# main.net
KiCad netlist of a schematic drawn in EAGLE
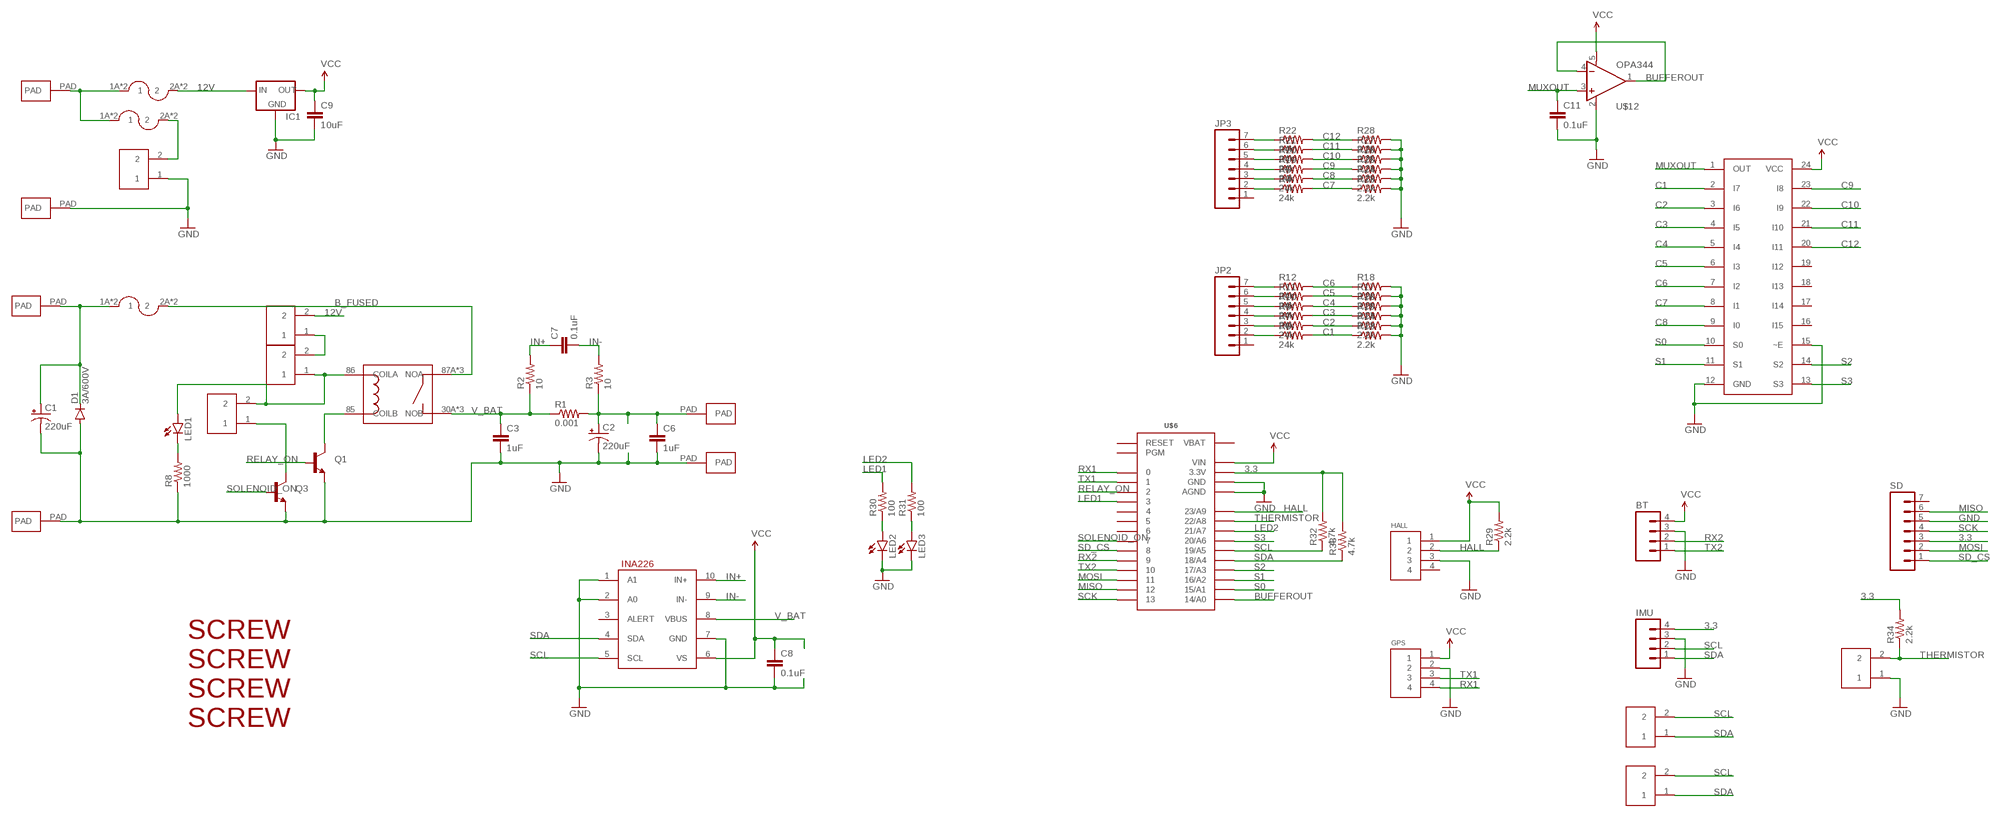
[diagram p0: schematic, sheet 1]

(export (version "E")
  (design (tool "Eeschema 10.0.6"))
  (components
    (comp (ref "BT")
      (value "M04PTH")
      (footprint "eagle-import:1X04")
      (libsource (lib "eagle-import") (part "M04PTH"))
    )
    (comp (ref "C1")
      (value "220uF")
      (footprint "eagle-import:CPOL-RADIAL-1000UF-25V")
      (libsource (lib "eagle-import") (part "CAP_POLPTH4"))
    )
    (comp (ref "C2")
      (value "220uF")
      (footprint "eagle-import:CPOL-RADIAL-1000UF-25V")
      (libsource (lib "eagle-import") (part "CAP_POLPTH4"))
    )
    (comp (ref "C3")
      (value "1uF")
      (footprint "eagle-import:1206")
      (libsource (lib "eagle-import") (part "CAP1206"))
    )
    (comp (ref "C6")
      (value "1uF")
      (footprint "eagle-import:1206")
      (libsource (lib "eagle-import") (part "CAP1206"))
    )
    (comp (ref "C7")
      (value "0.1uF")
      (footprint "eagle-import:0603-CAP")
      (libsource (lib "eagle-import") (part "SparkFun-Passives_CAP0603-CAP"))
    )
    (comp (ref "C8")
      (value "0.1uF")
      (footprint "eagle-import:0603-CAP")
      (libsource (lib "eagle-import") (part "SparkFun-Passives_CAP0603-CAP"))
    )
    (comp (ref "C9")
      (value "10uF")
      (footprint "eagle-import:0805")
      (libsource (lib "eagle-import") (part "SparkFun-Passives_CAP0805"))
    )
    (comp (ref "C11")
      (value "0.1uF")
      (footprint "eagle-import:0603-CAP")
      (libsource (lib "eagle-import") (part "SparkFun-Passives_CAP0603-CAP"))
    )
    (comp (ref "D1")
      (value "3A/600V")
      (footprint "eagle-import:SMC")
      (libsource (lib "eagle-import") (part "DIODEES3J"))
    )
    (comp (ref "GPS")
      (value "GPS")
      (footprint "eagle-import:4PINVALULOK")
      (libsource (lib "eagle-import") (part "HEADER4VALULOK"))
    )
    (comp (ref "HALL")
      (value "HEADER4VALULOK")
      (footprint "eagle-import:4PINVALULOK")
      (libsource (lib "eagle-import") (part "HEADER4VALULOK"))
    )
    (comp (ref "IC1")
      (value "V_REG_78XXSINK")
      (footprint "eagle-import:TO220-IGO")
      (libsource (lib "eagle-import") (part "V_REG_78XXSINK"))
    )
    (comp (ref "IMU")
      (value "M04PTH")
      (footprint "eagle-import:1X04")
      (libsource (lib "eagle-import") (part "M04PTH"))
    )
    (comp (ref "JP2")
      (value "M07")
      (footprint "eagle-import:1X07")
      (libsource (lib "eagle-import") (part "M07"))
    )
    (comp (ref "JP3")
      (value "M07")
      (footprint "eagle-import:1X07")
      (libsource (lib "eagle-import") (part "M07"))
    )
    (comp (ref "LED1")
      (value "LED1206")
      (footprint "eagle-import:LED-1206")
      (libsource (lib "eagle-import") (part "LED1206"))
    )
    (comp (ref "LED2")
      (value "LED1206")
      (footprint "eagle-import:LED-1206")
      (libsource (lib "eagle-import") (part "LED1206"))
    )
    (comp (ref "LED3")
      (value "LED1206")
      (footprint "eagle-import:LED-1206")
      (libsource (lib "eagle-import") (part "LED1206"))
    )
    (comp (ref "Q1")
      (value "TRANSISTOR_NPNSMD2")
      (footprint "eagle-import:SOT223")
      (libsource (lib "eagle-import") (part "TRANSISTOR_NPNSMD2"))
    )
    (comp (ref "Q3")
      (value "TRANSISTOR_NPNSMD2")
      (footprint "eagle-import:SOT223")
      (libsource (lib "eagle-import") (part "TRANSISTOR_NPNSMD2"))
    )
    (comp (ref "R1")
      (value "0.001")
      (footprint "eagle-import:R2512")
      (libsource (lib "eagle-import") (part "SparkFun-Resistors_RESISTOR2512"))
    )
    (comp (ref "R2")
      (value "10")
      (footprint "eagle-import:0603-RES")
      (libsource (lib "eagle-import") (part "RESISTOR0603-RES"))
    )
    (comp (ref "R3")
      (value "10")
      (footprint "eagle-import:0603-RES")
      (libsource (lib "eagle-import") (part "RESISTOR0603-RES"))
    )
    (comp (ref "R4")
      (value "24k")
      (footprint "eagle-import:0603-RES")
      (libsource (lib "eagle-import") (part "RESISTOR0603-RES"))
    )
    (comp (ref "R5")
      (value "24k")
      (footprint "eagle-import:0603-RES")
      (libsource (lib "eagle-import") (part "RESISTOR0603-RES"))
    )
    (comp (ref "R6")
      (value "24k")
      (footprint "eagle-import:0603-RES")
      (libsource (lib "eagle-import") (part "RESISTOR0603-RES"))
    )
    (comp (ref "R7")
      (value "24k")
      (footprint "eagle-import:0603-RES")
      (libsource (lib "eagle-import") (part "RESISTOR0603-RES"))
    )
    (comp (ref "R8")
      (value "1000")
      (footprint "eagle-import:0603-RES")
      (libsource (lib "eagle-import") (part "RESISTOR0603-RES"))
    )
    (comp (ref "R9")
      (value "24k")
      (footprint "eagle-import:0603-RES")
      (libsource (lib "eagle-import") (part "RESISTOR0603-RES"))
    )
    (comp (ref "R10")
      (value "24k")
      (footprint "eagle-import:0603-RES")
      (libsource (lib "eagle-import") (part "RESISTOR0603-RES"))
    )
    (comp (ref "R11")
      (value "24k")
      (footprint "eagle-import:0603-RES")
      (libsource (lib "eagle-import") (part "RESISTOR0603-RES"))
    )
    (comp (ref "R12")
      (value "24k")
      (footprint "eagle-import:0603-RES")
      (libsource (lib "eagle-import") (part "RESISTOR0603-RES"))
    )
    (comp (ref "R13")
      (value "2.2k")
      (footprint "eagle-import:0603-RES")
      (libsource (lib "eagle-import") (part "RESISTOR0603-RES"))
    )
    (comp (ref "R14")
      (value "2.2k")
      (footprint "eagle-import:0603-RES")
      (libsource (lib "eagle-import") (part "RESISTOR0603-RES"))
    )
    (comp (ref "R15")
      (value "2.2k")
      (footprint "eagle-import:0603-RES")
      (libsource (lib "eagle-import") (part "RESISTOR0603-RES"))
    )
    (comp (ref "R16")
      (value "2.2k")
      (footprint "eagle-import:0603-RES")
      (libsource (lib "eagle-import") (part "RESISTOR0603-RES"))
    )
    (comp (ref "R17")
      (value "2.2k")
      (footprint "eagle-import:0603-RES")
      (libsource (lib "eagle-import") (part "RESISTOR0603-RES"))
    )
    (comp (ref "R18")
      (value "2.2k")
      (footprint "eagle-import:0603-RES")
      (libsource (lib "eagle-import") (part "RESISTOR0603-RES"))
    )
    (comp (ref "R19")
      (value "24k")
      (footprint "eagle-import:0603-RES")
      (libsource (lib "eagle-import") (part "RESISTOR0603-RES"))
    )
    (comp (ref "R20")
      (value "24k")
      (footprint "eagle-import:0603-RES")
      (libsource (lib "eagle-import") (part "RESISTOR0603-RES"))
    )
    (comp (ref "R21")
      (value "24k")
      (footprint "eagle-import:0603-RES")
      (libsource (lib "eagle-import") (part "RESISTOR0603-RES"))
    )
    (comp (ref "R22")
      (value "24k")
      (footprint "eagle-import:0603-RES")
      (libsource (lib "eagle-import") (part "RESISTOR0603-RES"))
    )
    (comp (ref "R23")
      (value "2.2k")
      (footprint "eagle-import:0603-RES")
      (libsource (lib "eagle-import") (part "RESISTOR0603-RES"))
    )
    (comp (ref "R24")
      (value "2.2k")
      (footprint "eagle-import:0603-RES")
      (libsource (lib "eagle-import") (part "RESISTOR0603-RES"))
    )
    (comp (ref "R25")
      (value "2.2k")
      (footprint "eagle-import:0603-RES")
      (libsource (lib "eagle-import") (part "RESISTOR0603-RES"))
    )
    (comp (ref "R26")
      (value "2.2k")
      (footprint "eagle-import:0603-RES")
      (libsource (lib "eagle-import") (part "RESISTOR0603-RES"))
    )
    (comp (ref "R27")
      (value "2.2k")
      (footprint "eagle-import:0603-RES")
      (libsource (lib "eagle-import") (part "RESISTOR0603-RES"))
    )
    (comp (ref "R28")
      (value "2.2k")
      (footprint "eagle-import:0603-RES")
      (libsource (lib "eagle-import") (part "RESISTOR0603-RES"))
    )
    (comp (ref "R29")
      (value "2.2k")
      (footprint "eagle-import:0603-RES")
      (libsource (lib "eagle-import") (part "RESISTOR0603-RES"))
    )
    (comp (ref "R30")
      (value "100")
      (footprint "eagle-import:0603-RES")
      (libsource (lib "eagle-import") (part "RESISTOR0603-RES"))
    )
    (comp (ref "R31")
      (value "100")
      (footprint "eagle-import:0603-RES")
      (libsource (lib "eagle-import") (part "RESISTOR0603-RES"))
    )
    (comp (ref "R32")
      (value "4.7k")
      (footprint "eagle-import:0603-RES")
      (libsource (lib "eagle-import") (part "RESISTOR0603-RES"))
    )
    (comp (ref "R33")
      (value "4.7k")
      (footprint "eagle-import:0603-RES")
      (libsource (lib "eagle-import") (part "RESISTOR0603-RES"))
    )
    (comp (ref "R34")
      (value "2.2k")
      (footprint "eagle-import:0603-RES")
      (libsource (lib "eagle-import") (part "RESISTOR0603-RES"))
    )
    (comp (ref "SD")
      (value "M07")
      (footprint "eagle-import:1X07")
      (libsource (lib "eagle-import") (part "M07"))
    )
    (comp (ref "U$1")
      (value "INA226")
      (footprint "eagle-import:PSOP-10")
      (libsource (lib "eagle-import") (part "INA226"))
    )
    (comp (ref "U$2")
      (value "PAD")
      (footprint "eagle-import:PAD")
      (libsource (lib "eagle-import") (part "PAD"))
    )
    (comp (ref "U$3")
      (value "PAD")
      (footprint "eagle-import:PAD")
      (libsource (lib "eagle-import") (part "PAD"))
    )
    (comp (ref "U$4")
      (value "PAD")
      (footprint "eagle-import:PAD")
      (libsource (lib "eagle-import") (part "PAD"))
    )
    (comp (ref "U$5")
      (value "PAD")
      (footprint "eagle-import:PAD")
      (libsource (lib "eagle-import") (part "PAD"))
    )
    (comp (ref "U$6")
      (value "TEENSY_3.0_BASIC")
      (footprint "eagle-import:TEENSY_3.0_BASIC")
      (libsource (lib "eagle-import") (part "TEENSY_3.0_BASIC"))
    )
    (comp (ref "U$7")
      (value "RELAY")
      (footprint "eagle-import:PANASONIC_HP_RELAY")
      (libsource (lib "eagle-import") (part "RELAY"))
    )
    (comp (ref "U$8")
      (value "FUSE")
      (footprint "eagle-import:AUTO_FUSE")
      (libsource (lib "eagle-import") (part "FUSE"))
    )
    (comp (ref "U$9")
      (value "HEADER2")
      (footprint "eagle-import:2PINVALULOK")
      (libsource (lib "eagle-import") (part "HEADER2"))
    )
    (comp (ref "U$10")
      (value "HEADER2")
      (footprint "eagle-import:2PINVALULOK")
      (libsource (lib "eagle-import") (part "HEADER2"))
    )
    (comp (ref "U$11")
      (value "CD74HC4067")
      (footprint "eagle-import:SO-24DW")
      (libsource (lib "eagle-import") (part "CD74HC4067"))
    )
    (comp (ref "U$12")
      (value "OPA344")
      (footprint "eagle-import:SOT23-5")
      (libsource (lib "eagle-import") (part "OPA344"))
    )
    (comp (ref "U$13")
      (value "SCREW")
      (footprint "eagle-import:M3HOLE")
      (libsource (lib "eagle-import") (part "SCREW"))
    )
    (comp (ref "U$14")
      (value "SCREW")
      (footprint "eagle-import:M3HOLE")
      (libsource (lib "eagle-import") (part "SCREW"))
    )
    (comp (ref "U$15")
      (value "SCREW")
      (footprint "eagle-import:M3HOLE")
      (libsource (lib "eagle-import") (part "SCREW"))
    )
    (comp (ref "U$16")
      (value "SCREW")
      (footprint "eagle-import:M3HOLE")
      (libsource (lib "eagle-import") (part "SCREW"))
    )
    (comp (ref "U$17")
      (value "HEADER2")
      (footprint "eagle-import:2PINVALULOK")
      (libsource (lib "eagle-import") (part "HEADER2"))
    )
    (comp (ref "U$18")
      (value "FUSE")
      (footprint "eagle-import:AUTO_FUSE")
      (libsource (lib "eagle-import") (part "FUSE"))
    )
    (comp (ref "U$19")
      (value "HEADER2")
      (footprint "eagle-import:2PINVALULOK")
      (libsource (lib "eagle-import") (part "HEADER2"))
    )
    (comp (ref "U$20")
      (value "PAD")
      (footprint "eagle-import:PAD")
      (libsource (lib "eagle-import") (part "PAD"))
    )
    (comp (ref "U$21")
      (value "PAD")
      (footprint "eagle-import:PAD")
      (libsource (lib "eagle-import") (part "PAD"))
    )
    (comp (ref "U$22")
      (value "FUSE")
      (footprint "eagle-import:AUTO_FUSE")
      (libsource (lib "eagle-import") (part "FUSE"))
    )
    (comp (ref "U$23")
      (value "HEADER2")
      (footprint "eagle-import:2PINVALULOK")
      (libsource (lib "eagle-import") (part "HEADER2"))
    )
    (comp (ref "U$24")
      (value "HEADER2")
      (footprint "eagle-import:2PINVALULOK")
      (libsource (lib "eagle-import") (part "HEADER2"))
    )
    (comp (ref "U$25")
      (value "HEADER2")
      (footprint "eagle-import:2PINVALULOK")
      (libsource (lib "eagle-import") (part "HEADER2"))
    )
  )
  (nets
    (net (code "1") (name "/3.3") (class "Default")
      (node (ref "IMU") (pin "4") (pinfunction "4_4") (pintype "passive"))
      (node (ref "R32") (pin "2") (pinfunction "2_2") (pintype "passive"))
      (node (ref "R33") (pin "2") (pinfunction "2_2") (pintype "passive"))
      (node (ref "R34") (pin "2") (pinfunction "2_2") (pintype "passive"))
      (node (ref "SD") (pin "3") (pinfunction "3_3") (pintype "passive"))
      (node (ref "U$6") (pin "3.3V") (pinfunction "3.3V_3.3V") (pintype "power_in"))
      (node (ref "U$6") (pin "3.3V1") (pinfunction "3.3V_3.3V1") (pintype "power_in"))
    )
    (net (code "2") (name "/12V") (class "Default")
      (node (ref "IC1") (pin "IN") (pinfunction "IN_IN") (pintype "input"))
      (node (ref "U$10") (pin "2") (pinfunction "2_2") (pintype "bidirectional"))
      (node (ref "U$22") (pin "2A") (pinfunction "2_2A") (pintype "bidirectional"))
      (node (ref "U$22") (pin "2B") (pinfunction "2_2B") (pintype "bidirectional"))
    )
    (net (code "3") (name "/BUFFEROUT") (class "Default")
      (node (ref "U$12") (pin "1") (pinfunction "OUT_1") (pintype "output"))
      (node (ref "U$12") (pin "4") (pinfunction "-IN_4") (pintype "input"))
      (node (ref "U$6") (pin "14/A0") (pinfunction "14/A0_14/A0") (pintype "bidirectional"))
    )
    (net (code "4") (name "/B_FUSED") (class "Default")
      (node (ref "U$7") (pin "87A") (pinfunction "NOA_87A") (pintype "bidirectional"))
      (node (ref "U$7") (pin "87B") (pinfunction "NOA_87B") (pintype "bidirectional"))
      (node (ref "U$7") (pin "87C") (pinfunction "NOA_87C") (pintype "bidirectional"))
      (node (ref "U$8") (pin "2A") (pinfunction "2_2A") (pintype "bidirectional"))
      (node (ref "U$8") (pin "2B") (pinfunction "2_2B") (pintype "bidirectional"))
    )
    (net (code "5") (name "/C1") (class "Default")
      (node (ref "R13") (pin "1") (pinfunction "1_1") (pintype "passive"))
      (node (ref "R6") (pin "2") (pinfunction "2_2") (pintype "passive"))
      (node (ref "U$11") (pin "2") (pinfunction "I7_2") (pintype "bidirectional"))
    )
    (net (code "6") (name "/C2") (class "Default")
      (node (ref "R14") (pin "1") (pinfunction "1_1") (pintype "passive"))
      (node (ref "R7") (pin "2") (pinfunction "2_2") (pintype "passive"))
      (node (ref "U$11") (pin "3") (pinfunction "I6_3") (pintype "bidirectional"))
    )
    (net (code "7") (name "/C3") (class "Default")
      (node (ref "R15") (pin "1") (pinfunction "1_1") (pintype "passive"))
      (node (ref "R9") (pin "2") (pinfunction "2_2") (pintype "passive"))
      (node (ref "U$11") (pin "4") (pinfunction "I5_4") (pintype "bidirectional"))
    )
    (net (code "8") (name "/C4") (class "Default")
      (node (ref "R10") (pin "2") (pinfunction "2_2") (pintype "passive"))
      (node (ref "R16") (pin "1") (pinfunction "1_1") (pintype "passive"))
      (node (ref "U$11") (pin "5") (pinfunction "I4_5") (pintype "bidirectional"))
    )
    (net (code "9") (name "/C5") (class "Default")
      (node (ref "R11") (pin "2") (pinfunction "2_2") (pintype "passive"))
      (node (ref "R17") (pin "1") (pinfunction "1_1") (pintype "passive"))
      (node (ref "U$11") (pin "6") (pinfunction "I3_6") (pintype "bidirectional"))
    )
    (net (code "10") (name "/C6") (class "Default")
      (node (ref "R12") (pin "2") (pinfunction "2_2") (pintype "passive"))
      (node (ref "R18") (pin "1") (pinfunction "1_1") (pintype "passive"))
      (node (ref "U$11") (pin "7") (pinfunction "I2_7") (pintype "bidirectional"))
    )
    (net (code "11") (name "/C7") (class "Default")
      (node (ref "R23") (pin "1") (pinfunction "1_1") (pintype "passive"))
      (node (ref "R4") (pin "2") (pinfunction "2_2") (pintype "passive"))
      (node (ref "U$11") (pin "8") (pinfunction "I1_8") (pintype "bidirectional"))
    )
    (net (code "12") (name "/C8") (class "Default")
      (node (ref "R24") (pin "1") (pinfunction "1_1") (pintype "passive"))
      (node (ref "R5") (pin "2") (pinfunction "2_2") (pintype "passive"))
      (node (ref "U$11") (pin "9") (pinfunction "I0_9") (pintype "bidirectional"))
    )
    (net (code "13") (name "/C9") (class "Default")
      (node (ref "R19") (pin "2") (pinfunction "2_2") (pintype "passive"))
      (node (ref "R25") (pin "1") (pinfunction "1_1") (pintype "passive"))
      (node (ref "U$11") (pin "23") (pinfunction "I8_23") (pintype "bidirectional"))
    )
    (net (code "14") (name "/C10") (class "Default")
      (node (ref "R20") (pin "2") (pinfunction "2_2") (pintype "passive"))
      (node (ref "R26") (pin "1") (pinfunction "1_1") (pintype "passive"))
      (node (ref "U$11") (pin "22") (pinfunction "I9_22") (pintype "bidirectional"))
    )
    (net (code "15") (name "/C11") (class "Default")
      (node (ref "R21") (pin "2") (pinfunction "2_2") (pintype "passive"))
      (node (ref "R27") (pin "1") (pinfunction "1_1") (pintype "passive"))
      (node (ref "U$11") (pin "21") (pinfunction "I10_21") (pintype "bidirectional"))
    )
    (net (code "16") (name "/C12") (class "Default")
      (node (ref "R22") (pin "2") (pinfunction "2_2") (pintype "passive"))
      (node (ref "R28") (pin "1") (pinfunction "1_1") (pintype "passive"))
      (node (ref "U$11") (pin "20") (pinfunction "I11_20") (pintype "bidirectional"))
    )
    (net (code "17") (name "/HALL") (class "Default")
      (node (ref "HALL") (pin "2") (pinfunction "2_2") (pintype "bidirectional"))
      (node (ref "R29") (pin "1") (pinfunction "1_1") (pintype "passive"))
      (node (ref "U$6") (pin "23/A9") (pinfunction "23/A9_23/A9") (pintype "bidirectional"))
    )
    (net (code "18") (name "/IN+") (class "Default")
      (node (ref "C7") (pin "1") (pinfunction "1_1") (pintype "passive"))
      (node (ref "R2") (pin "2") (pinfunction "2_2") (pintype "passive"))
      (node (ref "U$1") (pin "10") (pinfunction "IN+_10") (pintype "bidirectional"))
    )
    (net (code "19") (name "/IN-") (class "Default")
      (node (ref "C7") (pin "2") (pinfunction "2_2") (pintype "passive"))
      (node (ref "R3") (pin "2") (pinfunction "2_2") (pintype "passive"))
      (node (ref "U$1") (pin "9") (pinfunction "IN-_9") (pintype "bidirectional"))
    )
    (net (code "20") (name "/LED1") (class "Default")
      (node (ref "R30") (pin "2") (pinfunction "2_2") (pintype "passive"))
      (node (ref "U$6") (pin "3") (pinfunction "3_3") (pintype "bidirectional"))
    )
    (net (code "21") (name "/LED2") (class "Default")
      (node (ref "R31") (pin "2") (pinfunction "2_2") (pintype "passive"))
      (node (ref "U$6") (pin "21/A7") (pinfunction "21/A7_21/A7") (pintype "bidirectional"))
    )
    (net (code "22") (name "/MISO") (class "Default")
      (node (ref "SD") (pin "6") (pinfunction "6_6") (pintype "passive"))
      (node (ref "U$6") (pin "12") (pinfunction "12_12") (pintype "bidirectional"))
    )
    (net (code "23") (name "/MOSI") (class "Default")
      (node (ref "SD") (pin "2") (pinfunction "2_2") (pintype "passive"))
      (node (ref "U$6") (pin "11") (pinfunction "11_11") (pintype "bidirectional"))
    )
    (net (code "24") (name "/MUXOUT") (class "Default")
      (node (ref "C11") (pin "1") (pinfunction "1_1") (pintype "passive"))
      (node (ref "U$11") (pin "1") (pinfunction "OUT_1") (pintype "bidirectional"))
      (node (ref "U$12") (pin "3") (pinfunction "+IN_3") (pintype "input"))
    )
    (net (code "25") (name "/RELAY_ON") (class "Default")
      (node (ref "Q1") (pin "1") (pinfunction "B_1") (pintype "passive"))
      (node (ref "U$6") (pin "2") (pinfunction "2_2") (pintype "bidirectional"))
    )
    (net (code "26") (name "/RX1") (class "Default")
      (node (ref "GPS") (pin "4") (pinfunction "4_4") (pintype "bidirectional"))
      (node (ref "U$6") (pin "0") (pinfunction "0_0") (pintype "bidirectional"))
    )
    (net (code "27") (name "/RX2") (class "Default")
      (node (ref "BT") (pin "2") (pinfunction "2_2") (pintype "passive"))
      (node (ref "U$6") (pin "9") (pinfunction "9_9") (pintype "bidirectional"))
    )
    (net (code "28") (name "/S0") (class "Default")
      (node (ref "U$11") (pin "10") (pinfunction "S0_10") (pintype "bidirectional"))
      (node (ref "U$6") (pin "15/A1") (pinfunction "15/A1_15/A1") (pintype "bidirectional"))
    )
    (net (code "29") (name "/S1") (class "Default")
      (node (ref "U$11") (pin "11") (pinfunction "S1_11") (pintype "bidirectional"))
      (node (ref "U$6") (pin "16/A2") (pinfunction "16/A2_16/A2") (pintype "bidirectional"))
    )
    (net (code "30") (name "/S2") (class "Default")
      (node (ref "U$11") (pin "14") (pinfunction "S2_14") (pintype "bidirectional"))
      (node (ref "U$6") (pin "17/A3") (pinfunction "17/A3_17/A3") (pintype "bidirectional"))
    )
    (net (code "31") (name "/S3") (class "Default")
      (node (ref "U$11") (pin "13") (pinfunction "S3_13") (pintype "bidirectional"))
      (node (ref "U$6") (pin "20/A6") (pinfunction "20/A6_20/A6") (pintype "bidirectional"))
    )
    (net (code "32") (name "/SCK") (class "Default")
      (node (ref "SD") (pin "4") (pinfunction "4_4") (pintype "passive"))
      (node (ref "U$6") (pin "13") (pinfunction "13_13") (pintype "bidirectional"))
    )
    (net (code "33") (name "/SCL") (class "Default")
      (node (ref "IMU") (pin "2") (pinfunction "2_2") (pintype "passive"))
      (node (ref "R32") (pin "1") (pinfunction "1_1") (pintype "passive"))
      (node (ref "U$1") (pin "5") (pinfunction "SCL_5") (pintype "bidirectional"))
      (node (ref "U$24") (pin "2") (pinfunction "2_2") (pintype "bidirectional"))
      (node (ref "U$25") (pin "2") (pinfunction "2_2") (pintype "bidirectional"))
      (node (ref "U$6") (pin "19/A5") (pinfunction "19/A5_19/A5") (pintype "bidirectional"))
    )
    (net (code "34") (name "/SDA") (class "Default")
      (node (ref "IMU") (pin "1") (pinfunction "1_1") (pintype "passive"))
      (node (ref "R33") (pin "1") (pinfunction "1_1") (pintype "passive"))
      (node (ref "U$1") (pin "4") (pinfunction "SDA_4") (pintype "bidirectional"))
      (node (ref "U$24") (pin "1") (pinfunction "1_1") (pintype "bidirectional"))
      (node (ref "U$25") (pin "1") (pinfunction "1_1") (pintype "bidirectional"))
      (node (ref "U$6") (pin "18/A4") (pinfunction "18/A4_18/A4") (pintype "bidirectional"))
    )
    (net (code "35") (name "/SD_CS") (class "Default")
      (node (ref "SD") (pin "1") (pinfunction "1_1") (pintype "passive"))
      (node (ref "U$6") (pin "8") (pinfunction "8_8") (pintype "bidirectional"))
    )
    (net (code "36") (name "/SOLENOID_ON") (class "Default")
      (node (ref "Q3") (pin "1") (pinfunction "B_1") (pintype "passive"))
      (node (ref "U$6") (pin "7") (pinfunction "7_7") (pintype "bidirectional"))
    )
    (net (code "37") (name "/THERMISTOR") (class "Default")
      (node (ref "R34") (pin "1") (pinfunction "1_1") (pintype "passive"))
      (node (ref "U$17") (pin "2") (pinfunction "2_2") (pintype "bidirectional"))
      (node (ref "U$6") (pin "22/A8") (pinfunction "22/A8_22/A8") (pintype "bidirectional"))
    )
    (net (code "38") (name "/TX1") (class "Default")
      (node (ref "GPS") (pin "3") (pinfunction "3_3") (pintype "bidirectional"))
      (node (ref "U$6") (pin "1") (pinfunction "1_1") (pintype "bidirectional"))
    )
    (net (code "39") (name "/TX2") (class "Default")
      (node (ref "BT") (pin "1") (pinfunction "1_1") (pintype "passive"))
      (node (ref "U$6") (pin "10") (pinfunction "10_10") (pintype "bidirectional"))
    )
    (net (code "40") (name "/VBAT") (class "Default")
      (node (ref "U$6") (pin "VBAT") (pinfunction "VBAT_VBAT") (pintype "power_in"))
    )
    (net (code "41") (name "/V_BAT") (class "Default")
      (node (ref "C3") (pin "1") (pinfunction "1_1") (pintype "passive"))
      (node (ref "R1") (pin "1") (pinfunction "1_1") (pintype "passive"))
      (node (ref "R2") (pin "1") (pinfunction "1_1") (pintype "passive"))
      (node (ref "U$1") (pin "8") (pinfunction "VBUS_8") (pintype "bidirectional"))
      (node (ref "U$7") (pin "30A") (pinfunction "NOB_30A") (pintype "bidirectional"))
      (node (ref "U$7") (pin "30B") (pinfunction "NOB_30B") (pintype "bidirectional"))
      (node (ref "U$7") (pin "30C") (pinfunction "NOB_30C") (pintype "bidirectional"))
    )
    (net (code "42") (name "GND") (class "Default")
      (node (ref "BT") (pin "3") (pinfunction "3_3") (pintype "passive"))
      (node (ref "C1") (pin "-") (pinfunction "-_-") (pintype "passive"))
      (node (ref "C11") (pin "2") (pinfunction "2_2") (pintype "passive"))
      (node (ref "C2") (pin "-") (pinfunction "-_-") (pintype "passive"))
      (node (ref "C3") (pin "2") (pinfunction "2_2") (pintype "passive"))
      (node (ref "C6") (pin "2") (pinfunction "2_2") (pintype "passive"))
      (node (ref "C8") (pin "2") (pinfunction "2_2") (pintype "passive"))
      (node (ref "C9") (pin "2") (pinfunction "2_2") (pintype "passive"))
      (node (ref "D1") (pin "A") (pinfunction "A_A") (pintype "passive"))
      (node (ref "GPS") (pin "2") (pinfunction "2_2") (pintype "bidirectional"))
      (node (ref "HALL") (pin "3") (pinfunction "3_3") (pintype "bidirectional"))
      (node (ref "IC1") (pin "GND") (pinfunction "GND_GND") (pintype "input"))
      (node (ref "IMU") (pin "3") (pinfunction "3_3") (pintype "passive"))
      (node (ref "LED2") (pin "C") (pinfunction "C_C") (pintype "passive"))
      (node (ref "LED3") (pin "C") (pinfunction "C_C") (pintype "passive"))
      (node (ref "Q1") (pin "3") (pinfunction "E_3") (pintype "passive"))
      (node (ref "Q3") (pin "3") (pinfunction "E_3") (pintype "passive"))
      (node (ref "R13") (pin "2") (pinfunction "2_2") (pintype "passive"))
      (node (ref "R14") (pin "2") (pinfunction "2_2") (pintype "passive"))
      (node (ref "R15") (pin "2") (pinfunction "2_2") (pintype "passive"))
      (node (ref "R16") (pin "2") (pinfunction "2_2") (pintype "passive"))
      (node (ref "R17") (pin "2") (pinfunction "2_2") (pintype "passive"))
      (node (ref "R18") (pin "2") (pinfunction "2_2") (pintype "passive"))
      (node (ref "R23") (pin "2") (pinfunction "2_2") (pintype "passive"))
      (node (ref "R24") (pin "2") (pinfunction "2_2") (pintype "passive"))
      (node (ref "R25") (pin "2") (pinfunction "2_2") (pintype "passive"))
      (node (ref "R26") (pin "2") (pinfunction "2_2") (pintype "passive"))
      (node (ref "R27") (pin "2") (pinfunction "2_2") (pintype "passive"))
      (node (ref "R28") (pin "2") (pinfunction "2_2") (pintype "passive"))
      (node (ref "R8") (pin "1") (pinfunction "1_1") (pintype "passive"))
      (node (ref "SD") (pin "5") (pinfunction "5_5") (pintype "passive"))
      (node (ref "U$1") (pin "1") (pinfunction "A1_1") (pintype "bidirectional"))
      (node (ref "U$1") (pin "2") (pinfunction "A0_2") (pintype "bidirectional"))
      (node (ref "U$1") (pin "7") (pinfunction "GND_7") (pintype "bidirectional"))
      (node (ref "U$11") (pin "12") (pinfunction "GND_12") (pintype "bidirectional"))
      (node (ref "U$11") (pin "15") (pinfunction "~{E}_15") (pintype "bidirectional"))
      (node (ref "U$12") (pin "2") (pinfunction "V-_2") (pintype "power_in"))
      (node (ref "U$17") (pin "1") (pinfunction "1_1") (pintype "bidirectional"))
      (node (ref "U$19") (pin "1") (pinfunction "1_1") (pintype "bidirectional"))
      (node (ref "U$21") (pin "PAD") (pinfunction "PAD_PAD") (pintype "bidirectional"))
      (node (ref "U$3") (pin "PAD") (pinfunction "PAD_PAD") (pintype "bidirectional"))
      (node (ref "U$5") (pin "PAD") (pinfunction "PAD_PAD") (pintype "bidirectional"))
      (node (ref "U$6") (pin "AGND") (pinfunction "AGND_AGND") (pintype "power_in"))
      (node (ref "U$6") (pin "GND") (pinfunction "GND_GND") (pintype "power_in"))
      (node (ref "U$6") (pin "GND1") (pinfunction "GND_GND1") (pintype "power_in"))
    )
    (net (code "43") (name "Net-(C1-Pad+)") (class "Default")
      (node (ref "C1") (pin "+") (pinfunction "+_+") (pintype "passive"))
      (node (ref "D1") (pin "C") (pinfunction "C_C") (pintype "passive"))
      (node (ref "U$2") (pin "PAD") (pinfunction "PAD_PAD") (pintype "bidirectional"))
      (node (ref "U$8") (pin "1A") (pinfunction "1_1A") (pintype "bidirectional"))
      (node (ref "U$8") (pin "1B") (pinfunction "1_1B") (pintype "bidirectional"))
    )
    (net (code "44") (name "Net-(C2-Pad+)") (class "Default")
      (node (ref "C2") (pin "+") (pinfunction "+_+") (pintype "passive"))
      (node (ref "C6") (pin "1") (pinfunction "1_1") (pintype "passive"))
      (node (ref "R1") (pin "2") (pinfunction "2_2") (pintype "passive"))
      (node (ref "R3") (pin "1") (pinfunction "1_1") (pintype "passive"))
      (node (ref "U$4") (pin "PAD") (pinfunction "PAD_PAD") (pintype "bidirectional"))
    )
    (net (code "45") (name "Net-(JP2-Pad2)") (class "Default")
      (node (ref "JP2") (pin "2") (pinfunction "2_2") (pintype "passive"))
      (node (ref "R6") (pin "1") (pinfunction "1_1") (pintype "passive"))
    )
    (net (code "46") (name "Net-(JP2-Pad3)") (class "Default")
      (node (ref "JP2") (pin "3") (pinfunction "3_3") (pintype "passive"))
      (node (ref "R7") (pin "1") (pinfunction "1_1") (pintype "passive"))
    )
    (net (code "47") (name "Net-(JP2-Pad4)") (class "Default")
      (node (ref "JP2") (pin "4") (pinfunction "4_4") (pintype "passive"))
      (node (ref "R9") (pin "1") (pinfunction "1_1") (pintype "passive"))
    )
    (net (code "48") (name "Net-(JP2-Pad5)") (class "Default")
      (node (ref "JP2") (pin "5") (pinfunction "5_5") (pintype "passive"))
      (node (ref "R10") (pin "1") (pinfunction "1_1") (pintype "passive"))
    )
    (net (code "49") (name "Net-(JP2-Pad6)") (class "Default")
      (node (ref "JP2") (pin "6") (pinfunction "6_6") (pintype "passive"))
      (node (ref "R11") (pin "1") (pinfunction "1_1") (pintype "passive"))
    )
    (net (code "50") (name "Net-(JP2-Pad7)") (class "Default")
      (node (ref "JP2") (pin "7") (pinfunction "7_7") (pintype "passive"))
      (node (ref "R12") (pin "1") (pinfunction "1_1") (pintype "passive"))
    )
    (net (code "51") (name "Net-(JP3-Pad2)") (class "Default")
      (node (ref "JP3") (pin "2") (pinfunction "2_2") (pintype "passive"))
      (node (ref "R4") (pin "1") (pinfunction "1_1") (pintype "passive"))
    )
    (net (code "52") (name "Net-(JP3-Pad3)") (class "Default")
      (node (ref "JP3") (pin "3") (pinfunction "3_3") (pintype "passive"))
      (node (ref "R5") (pin "1") (pinfunction "1_1") (pintype "passive"))
    )
    (net (code "53") (name "Net-(JP3-Pad4)") (class "Default")
      (node (ref "JP3") (pin "4") (pinfunction "4_4") (pintype "passive"))
      (node (ref "R19") (pin "1") (pinfunction "1_1") (pintype "passive"))
    )
    (net (code "54") (name "Net-(JP3-Pad5)") (class "Default")
      (node (ref "JP3") (pin "5") (pinfunction "5_5") (pintype "passive"))
      (node (ref "R20") (pin "1") (pinfunction "1_1") (pintype "passive"))
    )
    (net (code "55") (name "Net-(JP3-Pad6)") (class "Default")
      (node (ref "JP3") (pin "6") (pinfunction "6_6") (pintype "passive"))
      (node (ref "R21") (pin "1") (pinfunction "1_1") (pintype "passive"))
    )
    (net (code "56") (name "Net-(JP3-Pad7)") (class "Default")
      (node (ref "JP3") (pin "7") (pinfunction "7_7") (pintype "passive"))
      (node (ref "R22") (pin "1") (pinfunction "1_1") (pintype "passive"))
    )
    (net (code "57") (name "Net-(LED1-PadC)") (class "Default")
      (node (ref "LED1") (pin "C") (pinfunction "C_C") (pintype "passive"))
      (node (ref "R8") (pin "2") (pinfunction "2_2") (pintype "passive"))
    )
    (net (code "58") (name "Net-(LED2-PadA)") (class "Default")
      (node (ref "LED2") (pin "A") (pinfunction "A_A") (pintype "passive"))
      (node (ref "R30") (pin "1") (pinfunction "1_1") (pintype "passive"))
    )
    (net (code "59") (name "Net-(LED3-PadA)") (class "Default")
      (node (ref "LED3") (pin "A") (pinfunction "A_A") (pintype "passive"))
      (node (ref "R31") (pin "1") (pinfunction "1_1") (pintype "passive"))
    )
    (net (code "60") (name "Net-(Q1-C)") (class "Default")
      (node (ref "Q1") (pin "2") (pinfunction "C_2") (pintype "passive"))
      (node (ref "U$7") (pin "85") (pinfunction "COILB_85") (pintype "bidirectional"))
    )
    (net (code "61") (name "Net-(Q3-C)") (class "Default")
      (node (ref "Q3") (pin "2") (pinfunction "C_2") (pintype "passive"))
      (node (ref "U$23") (pin "1") (pinfunction "1_1") (pintype "bidirectional"))
    )
    (net (code "62") (name "Net-(U$7-COILA)") (class "Default")
      (node (ref "LED1") (pin "A") (pinfunction "A_A") (pintype "passive"))
      (node (ref "U$23") (pin "2") (pinfunction "2_2") (pintype "bidirectional"))
      (node (ref "U$7") (pin "86") (pinfunction "COILA_86") (pintype "bidirectional"))
      (node (ref "U$9") (pin "1") (pinfunction "1_1") (pintype "bidirectional"))
    )
    (net (code "63") (name "Net-(U$10-Pad1)") (class "Default")
      (node (ref "U$10") (pin "1") (pinfunction "1_1") (pintype "bidirectional"))
      (node (ref "U$9") (pin "2") (pinfunction "2_2") (pintype "bidirectional"))
    )
    (net (code "64") (name "Net-(U$18-1-Pad1A)") (class "Default")
      (node (ref "U$18") (pin "1A") (pinfunction "1_1A") (pintype "bidirectional"))
      (node (ref "U$18") (pin "1B") (pinfunction "1_1B") (pintype "bidirectional"))
      (node (ref "U$20") (pin "PAD") (pinfunction "PAD_PAD") (pintype "bidirectional"))
      (node (ref "U$22") (pin "1A") (pinfunction "1_1A") (pintype "bidirectional"))
      (node (ref "U$22") (pin "1B") (pinfunction "1_1B") (pintype "bidirectional"))
    )
    (net (code "65") (name "Net-(U$18-2-Pad2A)") (class "Default")
      (node (ref "U$18") (pin "2A") (pinfunction "2_2A") (pintype "bidirectional"))
      (node (ref "U$18") (pin "2B") (pinfunction "2_2B") (pintype "bidirectional"))
      (node (ref "U$19") (pin "2") (pinfunction "2_2") (pintype "bidirectional"))
    )
    (net (code "66") (name "VCC") (class "Default")
      (node (ref "BT") (pin "4") (pinfunction "4_4") (pintype "passive"))
      (node (ref "C8") (pin "1") (pinfunction "1_1") (pintype "passive"))
      (node (ref "C9") (pin "1") (pinfunction "1_1") (pintype "passive"))
      (node (ref "GPS") (pin "1") (pinfunction "1_1") (pintype "bidirectional"))
      (node (ref "HALL") (pin "1") (pinfunction "1_1") (pintype "bidirectional"))
      (node (ref "IC1") (pin "OUT") (pinfunction "OUT_OUT") (pintype "output"))
      (node (ref "R29") (pin "2") (pinfunction "2_2") (pintype "passive"))
      (node (ref "U$1") (pin "6") (pinfunction "VS_6") (pintype "bidirectional"))
      (node (ref "U$11") (pin "24") (pinfunction "VCC_24") (pintype "bidirectional"))
      (node (ref "U$12") (pin "5") (pinfunction "V+_5") (pintype "power_in"))
      (node (ref "U$6") (pin "VIN") (pinfunction "VIN_VIN") (pintype "power_in"))
    )
    (net (code "67") (name "unconnected-(HALL-Pad4)") (class "Default")
      (node (ref "HALL") (pin "4") (pinfunction "4_4") (pintype "bidirectional"))
    )
    (net (code "68") (name "unconnected-(JP2-Pad1)") (class "Default")
      (node (ref "JP2") (pin "1") (pinfunction "1_1") (pintype "passive"))
    )
    (net (code "69") (name "unconnected-(JP3-Pad1)") (class "Default")
      (node (ref "JP3") (pin "1") (pinfunction "1_1") (pintype "passive"))
    )
    (net (code "70") (name "unconnected-(SD-Pad7)") (class "Default")
      (node (ref "SD") (pin "7") (pinfunction "7_7") (pintype "passive"))
    )
    (net (code "71") (name "unconnected-(U$1-ALERT-Pad3)") (class "Default")
      (node (ref "U$1") (pin "3") (pinfunction "ALERT_3") (pintype "bidirectional"))
    )
    (net (code "72") (name "unconnected-(U$6-Pad4)") (class "Default")
      (node (ref "U$6") (pin "4") (pinfunction "4_4") (pintype "bidirectional"))
    )
    (net (code "73") (name "unconnected-(U$6-Pad5)") (class "Default")
      (node (ref "U$6") (pin "5") (pinfunction "5_5") (pintype "bidirectional"))
    )
    (net (code "74") (name "unconnected-(U$6-Pad6)") (class "Default")
      (node (ref "U$6") (pin "6") (pinfunction "6_6") (pintype "bidirectional"))
    )
    (net (code "75") (name "unconnected-(U$6-PadPGM)") (class "Default")
      (node (ref "U$6") (pin "PGM") (pinfunction "PGM_PGM") (pintype "bidirectional"))
    )
    (net (code "76") (name "unconnected-(U$6-PadRESET)") (class "Default")
      (node (ref "U$6") (pin "RESET") (pinfunction "RESET_RESET") (pintype "bidirectional"))
    )
    (net (code "77") (name "unconnected-(U$11-I12-Pad19)") (class "Default")
      (node (ref "U$11") (pin "19") (pinfunction "I12_19") (pintype "bidirectional"))
    )
    (net (code "78") (name "unconnected-(U$11-I13-Pad18)") (class "Default")
      (node (ref "U$11") (pin "18") (pinfunction "I13_18") (pintype "bidirectional"))
    )
    (net (code "79") (name "unconnected-(U$11-I14-Pad17)") (class "Default")
      (node (ref "U$11") (pin "17") (pinfunction "I14_17") (pintype "bidirectional"))
    )
    (net (code "80") (name "unconnected-(U$11-I15-Pad16)") (class "Default")
      (node (ref "U$11") (pin "16") (pinfunction "I15_16") (pintype "bidirectional"))
    )
  )
)
